# canSlaveV04_Flach.net
KiCad netlist of a schematic drawn in EAGLE
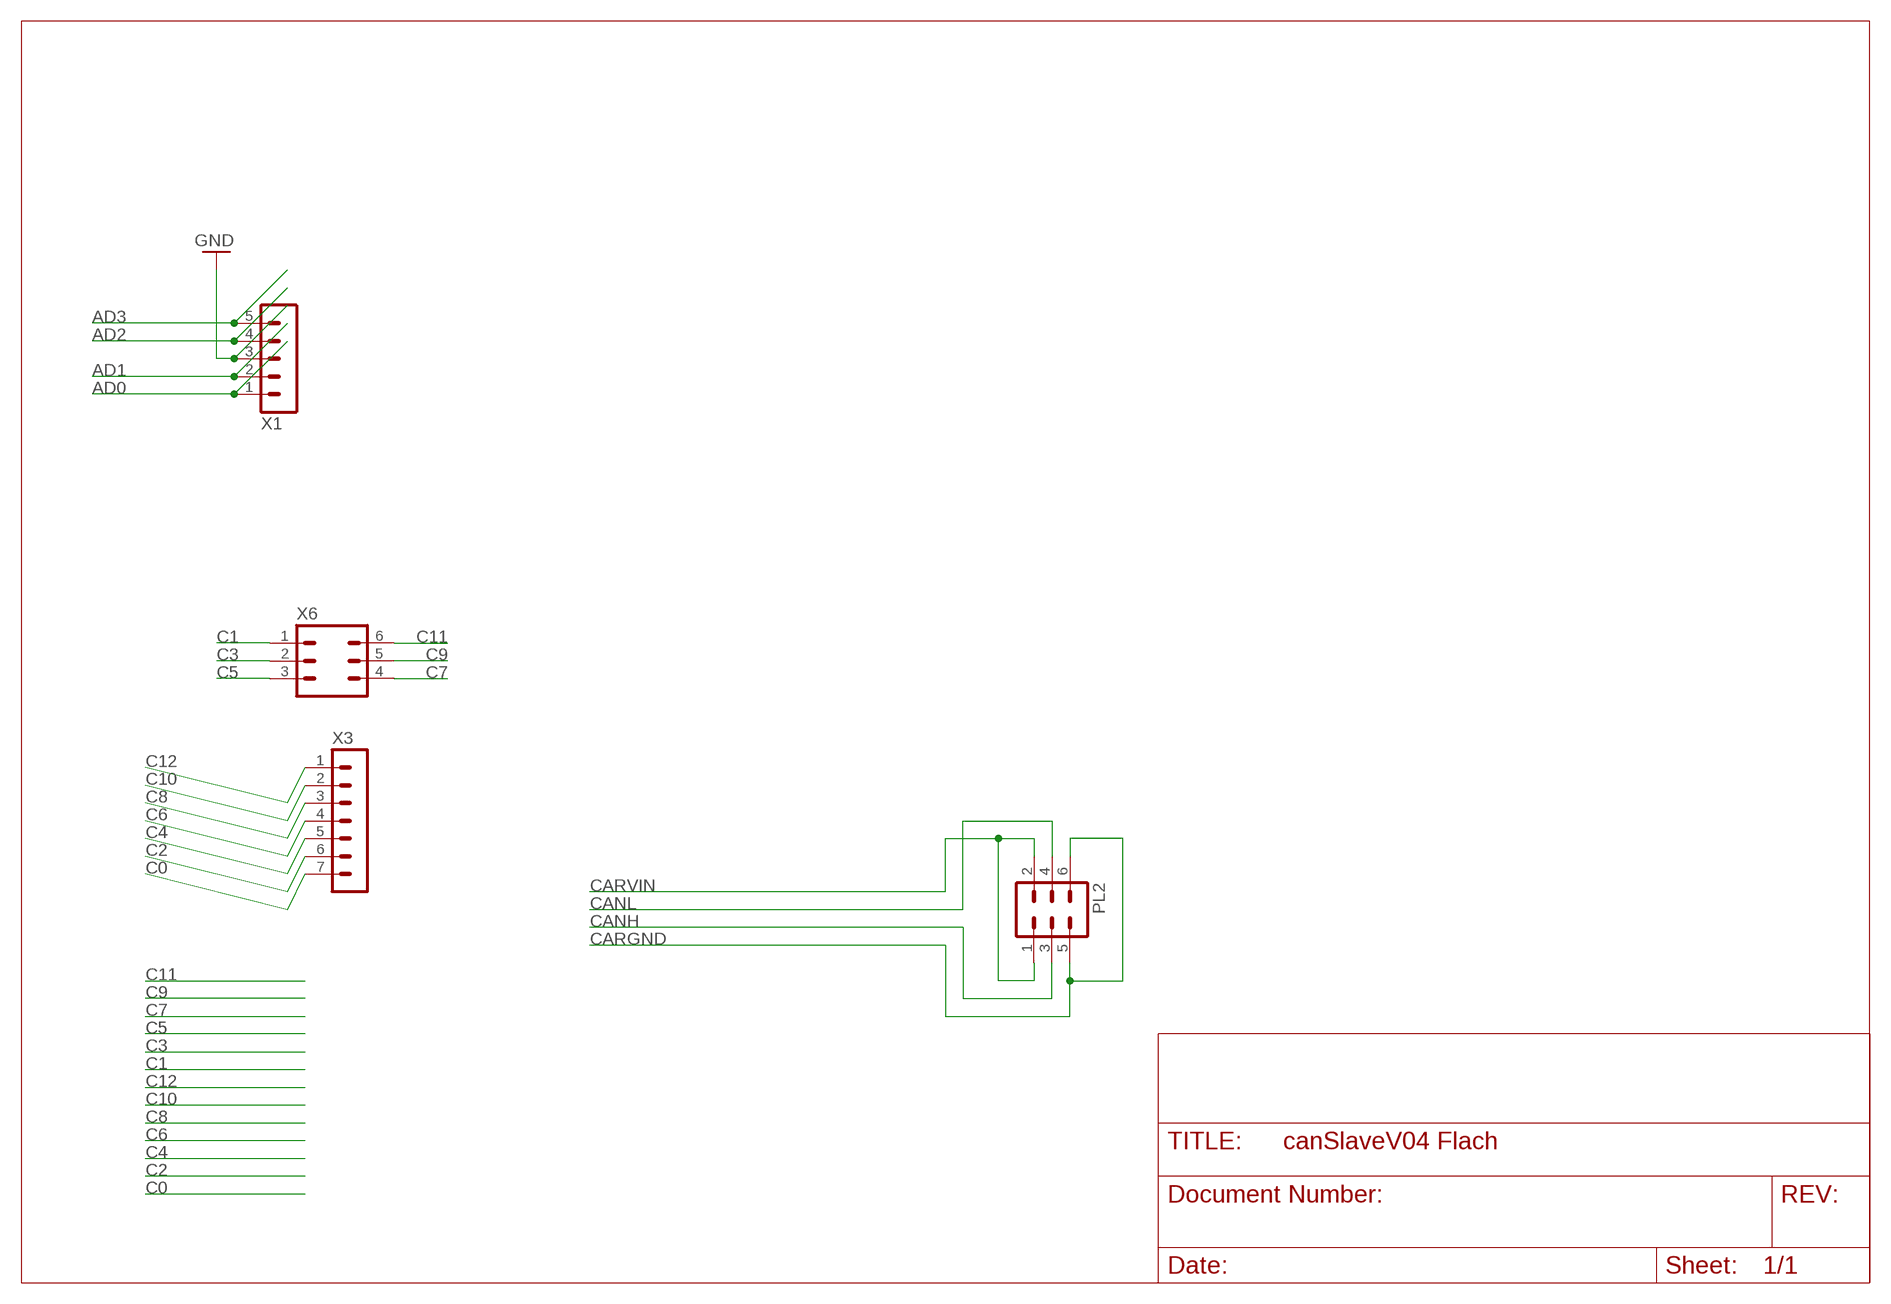
[diagram p0: schematic, sheet 1]

(export (version "E")
  (design (tool "Eeschema 10.0.6"))
  (components
    (comp (ref "PL2")
      (value "06H")
      (footprint "eagle-import:06H")
      (libsource (lib "eagle-import") (part "06H"))
    )
    (comp (ref "X1")
      (value "HEADER_POS5_43650-0500")
      (footprint "eagle-import:43650-0500")
      (libsource (lib "eagle-import") (part "HEADER_POS5_?43650-0500"))
    )
    (comp (ref "X3")
      (value "HEADER_POS7_43650-0700")
      (footprint "eagle-import:43650-0700")
      (libsource (lib "eagle-import") (part "HEADER_POS7_?43650-0700"))
    )
    (comp (ref "X6")
      (value "HEADER_POS6_43650-0600")
      (footprint "eagle-import:43650-0600")
      (libsource (lib "eagle-import") (part "HEADER_POS6_?43650-0600"))
    )
  )
  (nets
    (net (code "1") (name "/AD0") (class "Default")
      (node (ref "X1") (pin "1") (pinfunction "1_1") (pintype "passive"))
    )
    (net (code "2") (name "/AD1") (class "Default")
      (node (ref "X1") (pin "2") (pinfunction "2_2") (pintype "passive"))
    )
    (net (code "3") (name "/AD2") (class "Default")
      (node (ref "X1") (pin "4") (pinfunction "4_4") (pintype "passive"))
    )
    (net (code "4") (name "/AD3") (class "Default")
      (node (ref "X1") (pin "5") (pinfunction "5_5") (pintype "passive"))
    )
    (net (code "5") (name "/C0") (class "Default")
      (node (ref "X3") (pin "7") (pinfunction "7_7") (pintype "passive"))
    )
    (net (code "6") (name "/C1") (class "Default")
      (node (ref "X6") (pin "1") (pinfunction "1_1") (pintype "passive"))
    )
    (net (code "7") (name "/C2") (class "Default")
      (node (ref "X3") (pin "6") (pinfunction "6_6") (pintype "passive"))
    )
    (net (code "8") (name "/C3") (class "Default")
      (node (ref "X6") (pin "2") (pinfunction "2_2") (pintype "passive"))
    )
    (net (code "9") (name "/C4") (class "Default")
      (node (ref "X3") (pin "5") (pinfunction "5_5") (pintype "passive"))
    )
    (net (code "10") (name "/C5") (class "Default")
      (node (ref "X6") (pin "3") (pinfunction "3_3") (pintype "passive"))
    )
    (net (code "11") (name "/C6") (class "Default")
      (node (ref "X3") (pin "4") (pinfunction "4_4") (pintype "passive"))
    )
    (net (code "12") (name "/C7") (class "Default")
      (node (ref "X6") (pin "4") (pinfunction "4_4") (pintype "passive"))
    )
    (net (code "13") (name "/C8") (class "Default")
      (node (ref "X3") (pin "3") (pinfunction "3_3") (pintype "passive"))
    )
    (net (code "14") (name "/C9") (class "Default")
      (node (ref "X6") (pin "5") (pinfunction "5_5") (pintype "passive"))
    )
    (net (code "15") (name "/C10") (class "Default")
      (node (ref "X3") (pin "2") (pinfunction "2_2") (pintype "passive"))
    )
    (net (code "16") (name "/C11") (class "Default")
      (node (ref "X6") (pin "6") (pinfunction "6_6") (pintype "passive"))
    )
    (net (code "17") (name "/C12") (class "Default")
      (node (ref "X3") (pin "1") (pinfunction "1_1") (pintype "passive"))
    )
    (net (code "18") (name "/CANH") (class "Default")
      (node (ref "PL2") (pin "3") (pinfunction "3_3") (pintype "passive"))
    )
    (net (code "19") (name "/CANL") (class "Default")
      (node (ref "PL2") (pin "4") (pinfunction "4_4") (pintype "passive"))
    )
    (net (code "20") (name "/CARGND") (class "Default")
      (node (ref "PL2") (pin "5") (pinfunction "5_5") (pintype "passive"))
      (node (ref "PL2") (pin "6") (pinfunction "6_6") (pintype "passive"))
    )
    (net (code "21") (name "/CARVIN") (class "Default")
      (node (ref "PL2") (pin "1") (pinfunction "1_1") (pintype "passive"))
      (node (ref "PL2") (pin "2") (pinfunction "2_2") (pintype "passive"))
    )
    (net (code "22") (name "GND") (class "Default")
      (node (ref "X1") (pin "3") (pinfunction "3_3") (pintype "passive"))
    )
  )
)
